# TLC59731_Arduino_UNO_R3_Shield.net
KiCad netlist of a schematic drawn in EAGLE
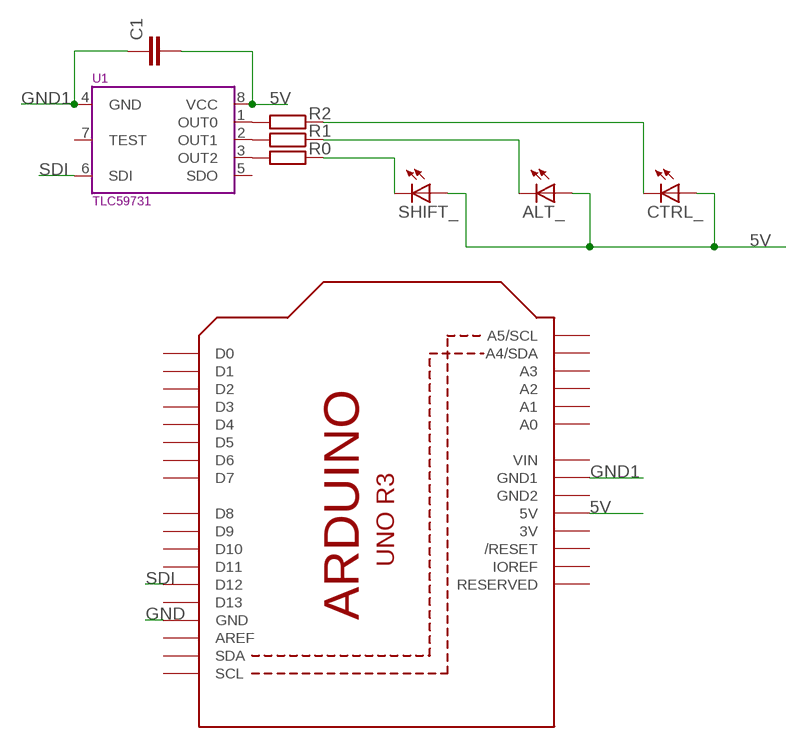
[diagram p0: schematic, sheet 1]

(export (version "E")
  (design (tool "Eeschema 10.0.6"))
  (components
    (comp (ref "ALT_")
      (value "LEDSMT1206")
      (footprint "eagle-import:1206")
      (libsource (lib "eagle-import") (part "LEDSMT1206"))
    )
    (comp (ref "C1")
      (value "CC0402")
      (footprint "eagle-import:C0402")
      (libsource (lib "eagle-import") (part "CC0402"))
    )
    (comp (ref "CTRL_")
      (value "LEDSMT1206")
      (footprint "eagle-import:1206")
      (libsource (lib "eagle-import") (part "LEDSMT1206"))
    )
    (comp (ref "M2")
      (value "ARDUINO_UNO_R3_EXT")
      (footprint "eagle-import:ARDUINO_UNO_R3_EXT")
      (libsource (lib "eagle-import") (part "ARDUINO_UNO_R3_EXT"))
    )
    (comp (ref "R0")
      (value "R_0402")
      (footprint "eagle-import:R0402")
      (libsource (lib "eagle-import") (part "R_0402"))
    )
    (comp (ref "R1")
      (value "R_0402")
      (footprint "eagle-import:R0402")
      (libsource (lib "eagle-import") (part "R_0402"))
    )
    (comp (ref "R2")
      (value "R_0402")
      (footprint "eagle-import:R0402")
      (libsource (lib "eagle-import") (part "R_0402"))
    )
    (comp (ref "SHIFT_")
      (value "LEDSMT1206")
      (footprint "eagle-import:1206")
      (libsource (lib "eagle-import") (part "LEDSMT1206"))
    )
    (comp (ref "U1")
      (value "TLC59731")
      (footprint "eagle-import:SOIC8_208MIL")
      (libsource (lib "eagle-import") (part "TLC59731"))
    )
  )
  (nets
    (net (code "1") (name "/3V") (class "Default")
      (node (ref "M2") (pin "3V") (pinfunction "3V_3V") (pintype "power_in"))
    )
    (net (code "2") (name "/5V") (class "Default")
      (node (ref "ALT_") (pin "A") (pinfunction "A_A") (pintype "passive"))
      (node (ref "C1") (pin "2") (pinfunction "2_2") (pintype "passive"))
      (node (ref "CTRL_") (pin "A") (pinfunction "A_A") (pintype "passive"))
      (node (ref "M2") (pin "5V") (pinfunction "5V_5V") (pintype "power_in"))
      (node (ref "SHIFT_") (pin "A") (pinfunction "A_A") (pintype "passive"))
      (node (ref "U1") (pin "8") (pinfunction "VCC_8") (pintype "bidirectional"))
    )
    (net (code "3") (name "/GND") (class "Default")
      (node (ref "M2") (pin "GND") (pinfunction "GND_GND") (pintype "power_in"))
    )
    (net (code "4") (name "/GND1") (class "Default")
      (node (ref "C1") (pin "1") (pinfunction "1_1") (pintype "passive"))
      (node (ref "M2") (pin "GND1") (pinfunction "GND1_GND1") (pintype "power_in"))
      (node (ref "U1") (pin "4") (pinfunction "GND_4") (pintype "bidirectional"))
    )
    (net (code "5") (name "/GND2") (class "Default")
      (node (ref "M2") (pin "GND2") (pinfunction "GND2_GND2") (pintype "power_in"))
    )
    (net (code "6") (name "/SDI") (class "Default")
      (node (ref "M2") (pin "D12") (pinfunction "D12_D12") (pintype "bidirectional"))
      (node (ref "U1") (pin "6") (pinfunction "SDI_6") (pintype "bidirectional"))
    )
    (net (code "7") (name "/VIN") (class "Default")
      (node (ref "M2") (pin "VIN") (pinfunction "VIN_VIN") (pintype "power_in"))
    )
    (net (code "8") (name "Net-(ALT_-PadC)") (class "Default")
      (node (ref "ALT_") (pin "C") (pinfunction "C_C") (pintype "passive"))
      (node (ref "R1") (pin "1") (pinfunction "1_1") (pintype "passive"))
    )
    (net (code "9") (name "Net-(CTRL_-PadC)") (class "Default")
      (node (ref "CTRL_") (pin "C") (pinfunction "C_C") (pintype "passive"))
      (node (ref "R2") (pin "1") (pinfunction "1_1") (pintype "passive"))
    )
    (net (code "10") (name "Net-(R0-Pad1)") (class "Default")
      (node (ref "R0") (pin "1") (pinfunction "1_1") (pintype "passive"))
      (node (ref "SHIFT_") (pin "C") (pinfunction "C_C") (pintype "passive"))
    )
    (net (code "11") (name "Net-(U1-OUT0)") (class "Default")
      (node (ref "R2") (pin "2") (pinfunction "2_2") (pintype "passive"))
      (node (ref "U1") (pin "1") (pinfunction "OUT0_1") (pintype "bidirectional"))
    )
    (net (code "12") (name "Net-(U1-OUT1)") (class "Default")
      (node (ref "R1") (pin "2") (pinfunction "2_2") (pintype "passive"))
      (node (ref "U1") (pin "2") (pinfunction "OUT1_2") (pintype "bidirectional"))
    )
    (net (code "13") (name "Net-(U1-OUT2)") (class "Default")
      (node (ref "R0") (pin "2") (pinfunction "2_2") (pintype "passive"))
      (node (ref "U1") (pin "3") (pinfunction "OUT2_3") (pintype "bidirectional"))
    )
    (net (code "14") (name "unconnected-(M2-A4{slash}SDA-PadA4)") (class "Default")
      (node (ref "M2") (pin "A4") (pinfunction "A4/SDA_A4") (pintype "bidirectional"))
    )
    (net (code "15") (name "unconnected-(M2-A5{slash}SCL-PadA5)") (class "Default")
      (node (ref "M2") (pin "A5") (pinfunction "A5/SCL_A5") (pintype "bidirectional"))
    )
    (net (code "16") (name "unconnected-(M2-PadA0)") (class "Default")
      (node (ref "M2") (pin "A0") (pinfunction "A0_A0") (pintype "bidirectional"))
    )
    (net (code "17") (name "unconnected-(M2-PadA1)") (class "Default")
      (node (ref "M2") (pin "A1") (pinfunction "A1_A1") (pintype "bidirectional"))
    )
    (net (code "18") (name "unconnected-(M2-PadA2)") (class "Default")
      (node (ref "M2") (pin "A2") (pinfunction "A2_A2") (pintype "bidirectional"))
    )
    (net (code "19") (name "unconnected-(M2-PadA3)") (class "Default")
      (node (ref "M2") (pin "A3") (pinfunction "A3_A3") (pintype "bidirectional"))
    )
    (net (code "20") (name "unconnected-(M2-PadAREF)") (class "Default")
      (node (ref "M2") (pin "AREF") (pinfunction "AREF_AREF") (pintype "bidirectional"))
    )
    (net (code "21") (name "unconnected-(M2-PadD0)") (class "Default")
      (node (ref "M2") (pin "D0") (pinfunction "D0_D0") (pintype "bidirectional"))
    )
    (net (code "22") (name "unconnected-(M2-PadD1)") (class "Default")
      (node (ref "M2") (pin "D1") (pinfunction "D1_D1") (pintype "bidirectional"))
    )
    (net (code "23") (name "unconnected-(M2-PadD2)") (class "Default")
      (node (ref "M2") (pin "D2") (pinfunction "D2_D2") (pintype "bidirectional"))
    )
    (net (code "24") (name "unconnected-(M2-PadD3)") (class "Default")
      (node (ref "M2") (pin "D3") (pinfunction "D3_D3") (pintype "bidirectional"))
    )
    (net (code "25") (name "unconnected-(M2-PadD4)") (class "Default")
      (node (ref "M2") (pin "D4") (pinfunction "D4_D4") (pintype "bidirectional"))
    )
    (net (code "26") (name "unconnected-(M2-PadD5)") (class "Default")
      (node (ref "M2") (pin "D5") (pinfunction "D5_D5") (pintype "bidirectional"))
    )
    (net (code "27") (name "unconnected-(M2-PadD6)") (class "Default")
      (node (ref "M2") (pin "D6") (pinfunction "D6_D6") (pintype "bidirectional"))
    )
    (net (code "28") (name "unconnected-(M2-PadD7)") (class "Default")
      (node (ref "M2") (pin "D7") (pinfunction "D7_D7") (pintype "bidirectional"))
    )
    (net (code "29") (name "unconnected-(M2-PadD8)") (class "Default")
      (node (ref "M2") (pin "D8") (pinfunction "D8_D8") (pintype "bidirectional"))
    )
    (net (code "30") (name "unconnected-(M2-PadD9)") (class "Default")
      (node (ref "M2") (pin "D9") (pinfunction "D9_D9") (pintype "bidirectional"))
    )
    (net (code "31") (name "unconnected-(M2-PadD10)") (class "Default")
      (node (ref "M2") (pin "D10") (pinfunction "D10_D10") (pintype "bidirectional"))
    )
    (net (code "32") (name "unconnected-(M2-PadD11)") (class "Default")
      (node (ref "M2") (pin "D11") (pinfunction "D11_D11") (pintype "bidirectional"))
    )
    (net (code "33") (name "unconnected-(M2-PadD13)") (class "Default")
      (node (ref "M2") (pin "D13") (pinfunction "D13_D13") (pintype "bidirectional"))
    )
    (net (code "34") (name "unconnected-(M2-PadIOREF)") (class "Default")
      (node (ref "M2") (pin "IOREF") (pinfunction "IOREF_IOREF") (pintype "output"))
    )
    (net (code "35") (name "unconnected-(M2-PadRESERVED)") (class "Default")
      (node (ref "M2") (pin "RESERVED") (pinfunction "RESERVED_RESERVED") (pintype "no_connect"))
    )
    (net (code "36") (name "unconnected-(M2-PadSCL)") (class "Default")
      (node (ref "M2") (pin "SCL") (pinfunction "SCL_SCL") (pintype "bidirectional"))
    )
    (net (code "37") (name "unconnected-(M2-PadSDA)") (class "Default")
      (node (ref "M2") (pin "SDA") (pinfunction "SDA_SDA") (pintype "bidirectional"))
    )
    (net (code "38") (name "unconnected-(M2-{slash}RESET-PadRESET)") (class "Default")
      (node (ref "M2") (pin "RESET") (pinfunction "/RESET_RESET") (pintype "bidirectional"))
    )
    (net (code "39") (name "unconnected-(U1-SDO-Pad5)") (class "Default")
      (node (ref "U1") (pin "5") (pinfunction "SDO_5") (pintype "bidirectional"))
    )
    (net (code "40") (name "unconnected-(U1-TEST-Pad7)") (class "Default")
      (node (ref "U1") (pin "7") (pinfunction "TEST_7") (pintype "bidirectional"))
    )
  )
)
